# Sheet1.net
KiCad netlist of a schematic drawn in Altium Designer
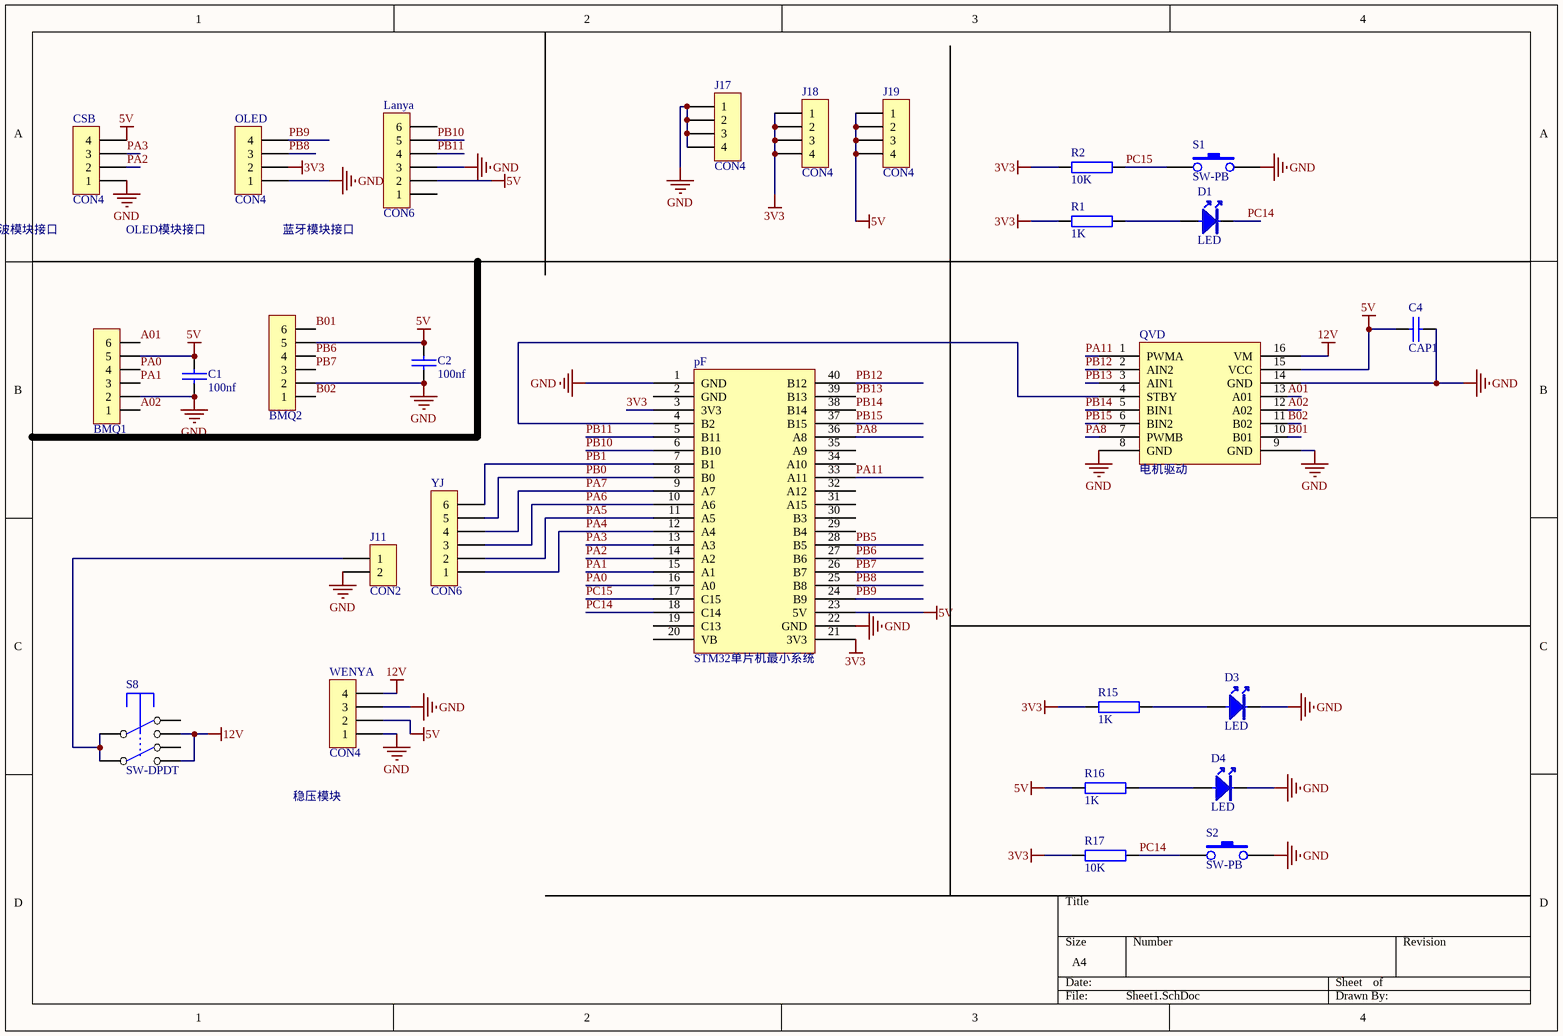
[diagram p0: Sheet1.SchDoc]

(export (version "E")
  (design (tool "Eeschema 10.0.6"))
  (components
    (comp (ref "BMQ1")
      (value "HDR-1X6")
      (footprint "XH2.54-WI-6P")
      (description "6P接插件")
      (fields (field (name "版权归属") "封装库来自淘宝 ID：黄晶宝石"))
      (libsource (lib "5.3 - 接插件-脚距2.54 (100mil) ") (part "Header 6"))
    )
    (comp (ref "BMQ2")
      (value "HDR-1X6")
      (footprint "XH2.54-WI-6P")
      (description "6P接插件")
      (fields (field (name "版权归属") "封装库来自淘宝 ID：黄晶宝石"))
      (libsource (lib "5.3 - 接插件-脚距2.54 (100mil) ") (part "Header 6"))
    )
    (comp (ref "C1") (value "100nf") (footprint "0603") (libsource (lib "电容") (part "CAP1")))
    (comp (ref "C2") (value "100nf") (footprint "0603") (libsource (lib "电容") (part "CAP1")))
    (comp (ref "C4") (value "CAP1") (footprint "0603") (libsource (lib "电容") (part "CAP1")))
    (comp (ref "CSB")
      (value "CON4")
      (footprint "HDR2.54-M-LI-4P")
      (description "Connector")
      (libsource (lib "接口") (part "CON4"))
    )
    (comp (ref "D1") (value "LED") (footprint "LED_0805") (libsource (lib "二极管") (part "LED")))
    (comp (ref "D3") (value "LED") (footprint "LED_0805") (libsource (lib "二极管") (part "LED")))
    (comp (ref "D4") (value "LED") (footprint "LED_0805") (libsource (lib "二极管") (part "LED")))
    (comp (ref "J11")
      (value "CON2")
      (footprint "KF128-5.08-2P")
      (description "Connector")
      (libsource (lib "接口") (part "CON2"))
    )
    (comp (ref "J17")
      (value "CON4")
      (footprint "sip-4")
      (description "Connector")
      (libsource (lib "排针") (part "CON4"))
    )
    (comp (ref "J18")
      (value "CON4")
      (footprint "sip-4")
      (description "Connector")
      (libsource (lib "排针") (part "CON4"))
    )
    (comp (ref "J19")
      (value "CON4")
      (footprint "sip-4")
      (description "Connector")
      (libsource (lib "排针") (part "CON4"))
    )
    (comp (ref "Lanya")
      (value "CON6")
      (footprint "HDR2.54-M-LI-6P")
      (description "Connector")
      (libsource (lib "接口") (part "CON6"))
    )
    (comp (ref "OLED")
      (value "CON4")
      (footprint "OLED")
      (description "Connector")
      (libsource (lib "接口") (part "CON4"))
    )
    (comp (ref "p")
      (value "STM32单片机最小系统")
      (footprint "PCBComponent_1 - duplicate")
      (libsource (lib "Schlib1") (part "Component_1"))
    )
    (comp (ref "QVD") (value "电机驱动") (footprint "DIP16P") (libsource (lib "Schlib2") (part "Component_1")))
    (comp (ref "R1") (value "1K") (footprint "0603") (description "电阻") (libsource (lib "电阻") (part "RES")))
    (comp (ref "R2") (value "10K") (footprint "0603") (description "电阻") (libsource (lib "电阻") (part "RES")))
    (comp (ref "R15") (value "1K") (footprint "0603") (description "电阻") (libsource (lib "电阻") (part "RES")))
    (comp (ref "R16") (value "1K") (footprint "0603") (description "电阻") (libsource (lib "电阻") (part "RES")))
    (comp (ref "R17") (value "10K") (footprint "0603") (description "电阻") (libsource (lib "电阻") (part "RES")))
    (comp (ref "S1") (value "SW-PB") (footprint "SW6*6") (libsource (lib "开关") (part "SW-PB")))
    (comp (ref "S2") (value "SW-PB") (footprint "SW6*6") (libsource (lib "开关") (part "SW-PB")))
    (comp (ref "S8") (value "SW-DPDT") (footprint "SWH7*7") (libsource (lib "开关.~(2)") (part "SW-DPDT")))
    (comp (ref "WENYA")
      (value "CON4")
      (footprint "WEI YA")
      (description "Connector")
      (libsource (lib "接口") (part "CON4"))
    )
    (comp (ref "YJ")
      (value "CON6")
      (footprint "sip-6")
      (description "Connector")
      (libsource (lib "排针") (part "CON6"))
    )
  )
  (nets
    (net (code "1") (name "/A01") (class "Default")
      (node (ref "BMQ1") (pin "6") (pinfunction "6_6") (pintype "passive"))
      (node (ref "QVD") (pin "13") (pinfunction "A01_13") (pintype "passive"))
    )
    (net (code "2") (name "/A02") (class "Default")
      (node (ref "BMQ1") (pin "1") (pinfunction "1_1") (pintype "passive"))
      (node (ref "QVD") (pin "12") (pinfunction "A02_12") (pintype "passive"))
    )
    (net (code "3") (name "/B01") (class "Default")
      (node (ref "BMQ2") (pin "6") (pinfunction "6_6") (pintype "passive"))
      (node (ref "QVD") (pin "10") (pinfunction "B01_10") (pintype "passive"))
    )
    (net (code "4") (name "/B02") (class "Default")
      (node (ref "BMQ2") (pin "1") (pinfunction "1_1") (pintype "passive"))
      (node (ref "QVD") (pin "11") (pinfunction "B02_11") (pintype "passive"))
    )
    (net (code "5") (name "/PA0") (class "Default")
      (node (ref "BMQ1") (pin "4") (pinfunction "4_4") (pintype "passive"))
      (node (ref "p") (pin "16") (pinfunction "A0_16") (pintype "passive"))
    )
    (net (code "6") (name "/PA1") (class "Default")
      (node (ref "BMQ1") (pin "3") (pinfunction "3_3") (pintype "passive"))
      (node (ref "p") (pin "15") (pinfunction "A1_15") (pintype "passive"))
    )
    (net (code "7") (name "/PA2") (class "Default")
      (node (ref "CSB") (pin "2") (pinfunction "2_2") (pintype "passive"))
      (node (ref "p") (pin "14") (pinfunction "A2_14") (pintype "passive"))
    )
    (net (code "8") (name "/PA3") (class "Default")
      (node (ref "CSB") (pin "3") (pinfunction "3_3") (pintype "passive"))
      (node (ref "p") (pin "13") (pinfunction "A3_13") (pintype "passive"))
    )
    (net (code "9") (name "/PA4") (class "Default")
      (node (ref "YJ") (pin "1") (pinfunction "1_1") (pintype "passive"))
      (node (ref "p") (pin "12") (pinfunction "A4_12") (pintype "passive"))
    )
    (net (code "10") (name "/PA5") (class "Default")
      (node (ref "YJ") (pin "2") (pinfunction "2_2") (pintype "passive"))
      (node (ref "p") (pin "11") (pinfunction "A5_11") (pintype "passive"))
    )
    (net (code "11") (name "/PA6") (class "Default")
      (node (ref "YJ") (pin "3") (pinfunction "3_3") (pintype "passive"))
      (node (ref "p") (pin "10") (pinfunction "A6_10") (pintype "passive"))
    )
    (net (code "12") (name "/PA7") (class "Default")
      (node (ref "YJ") (pin "4") (pinfunction "4_4") (pintype "passive"))
      (node (ref "p") (pin "9") (pinfunction "A7_9") (pintype "passive"))
    )
    (net (code "13") (name "/PA8") (class "Default")
      (node (ref "QVD") (pin "7") (pinfunction "PWMB_7") (pintype "passive"))
      (node (ref "p") (pin "36") (pinfunction "A8_36") (pintype "passive"))
    )
    (net (code "14") (name "/PA11") (class "Default")
      (node (ref "QVD") (pin "1") (pinfunction "PWMA_1") (pintype "passive"))
      (node (ref "p") (pin "33") (pinfunction "A11_33") (pintype "passive"))
    )
    (net (code "15") (name "/PB0") (class "Default")
      (node (ref "YJ") (pin "5") (pinfunction "5_5") (pintype "passive"))
      (node (ref "p") (pin "8") (pinfunction "B0_8") (pintype "passive"))
    )
    (net (code "16") (name "/PB1") (class "Default")
      (node (ref "YJ") (pin "6") (pinfunction "6_6") (pintype "passive"))
      (node (ref "p") (pin "7") (pinfunction "B1_7") (pintype "passive"))
    )
    (net (code "17") (name "/PB5") (class "Default")
      (node (ref "p") (pin "28") (pinfunction "B5_28") (pintype "passive"))
    )
    (net (code "18") (name "/PB6") (class "Default")
      (node (ref "BMQ2") (pin "4") (pinfunction "4_4") (pintype "passive"))
      (node (ref "p") (pin "27") (pinfunction "B6_27") (pintype "passive"))
    )
    (net (code "19") (name "/PB7") (class "Default")
      (node (ref "BMQ2") (pin "3") (pinfunction "3_3") (pintype "passive"))
      (node (ref "p") (pin "26") (pinfunction "B7_26") (pintype "passive"))
    )
    (net (code "20") (name "/PB8") (class "Default")
      (node (ref "OLED") (pin "3") (pinfunction "3_3") (pintype "passive"))
      (node (ref "p") (pin "25") (pinfunction "B8_25") (pintype "passive"))
    )
    (net (code "21") (name "/PB9") (class "Default")
      (node (ref "OLED") (pin "4") (pinfunction "4_4") (pintype "passive"))
      (node (ref "p") (pin "24") (pinfunction "B9_24") (pintype "passive"))
    )
    (net (code "22") (name "/PB10") (class "Default")
      (node (ref "Lanya") (pin "5") (pinfunction "5_5") (pintype "passive"))
      (node (ref "p") (pin "6") (pinfunction "B10_6") (pintype "passive"))
    )
    (net (code "23") (name "/PB11") (class "Default")
      (node (ref "Lanya") (pin "4") (pinfunction "4_4") (pintype "passive"))
      (node (ref "p") (pin "5") (pinfunction "B11_5") (pintype "passive"))
    )
    (net (code "24") (name "/PB12") (class "Default")
      (node (ref "QVD") (pin "2") (pinfunction "AIN2_2") (pintype "passive"))
      (node (ref "p") (pin "40") (pinfunction "B12_40") (pintype "passive"))
    )
    (net (code "25") (name "/PB13") (class "Default")
      (node (ref "QVD") (pin "3") (pinfunction "AIN1_3") (pintype "passive"))
      (node (ref "p") (pin "39") (pinfunction "B13_39") (pintype "passive"))
    )
    (net (code "26") (name "/PB14") (class "Default")
      (node (ref "QVD") (pin "5") (pinfunction "BIN1_5") (pintype "passive"))
      (node (ref "p") (pin "38") (pinfunction "B14_38") (pintype "passive"))
    )
    (net (code "27") (name "/PB15") (class "Default")
      (node (ref "QVD") (pin "6") (pinfunction "BIN2_6") (pintype "passive"))
      (node (ref "p") (pin "37") (pinfunction "B15_37") (pintype "passive"))
    )
    (net (code "28") (name "/PC14") (class "Default")
      (node (ref "D1") (pin "2") (pinfunction "2_2") (pintype "passive"))
      (node (ref "R17") (pin "2") (pinfunction "2_2") (pintype "passive"))
      (node (ref "S2") (pin "1") (pinfunction "1_1") (pintype "passive"))
      (node (ref "p") (pin "18") (pinfunction "C14_18") (pintype "passive"))
    )
    (net (code "29") (name "/PC15") (class "Default")
      (node (ref "R2") (pin "2") (pinfunction "2_2") (pintype "passive"))
      (node (ref "S1") (pin "1") (pinfunction "1_1") (pintype "passive"))
      (node (ref "p") (pin "17") (pinfunction "C15_17") (pintype "passive"))
    )
    (net (code "30") (name "3V3") (class "Default")
      (node (ref "J18") (pin "1") (pinfunction "1_1") (pintype "passive"))
      (node (ref "J18") (pin "2") (pinfunction "2_2") (pintype "passive"))
      (node (ref "J18") (pin "3") (pinfunction "3_3") (pintype "passive"))
      (node (ref "J18") (pin "4") (pinfunction "4_4") (pintype "passive"))
      (node (ref "OLED") (pin "2") (pinfunction "2_2") (pintype "passive"))
      (node (ref "R1") (pin "1") (pinfunction "1_1") (pintype "passive"))
      (node (ref "R15") (pin "1") (pinfunction "1_1") (pintype "passive"))
      (node (ref "R17") (pin "1") (pinfunction "1_1") (pintype "passive"))
      (node (ref "R2") (pin "1") (pinfunction "1_1") (pintype "passive"))
      (node (ref "p") (pin "21") (pinfunction "3V3_21") (pintype "passive"))
      (node (ref "p") (pin "3") (pinfunction "3V3_3") (pintype "passive"))
    )
    (net (code "31") (name "5V") (class "Default")
      (node (ref "BMQ1") (pin "5") (pinfunction "5_5") (pintype "passive"))
      (node (ref "BMQ2") (pin "5") (pinfunction "5_5") (pintype "passive"))
      (node (ref "C1") (pin "1") (pinfunction "1_1") (pintype "passive"))
      (node (ref "C2") (pin "1") (pinfunction "1_1") (pintype "passive"))
      (node (ref "C4") (pin "1") (pinfunction "1_1") (pintype "passive"))
      (node (ref "CSB") (pin "4") (pinfunction "4_4") (pintype "passive"))
      (node (ref "J19") (pin "1") (pinfunction "1_1") (pintype "passive"))
      (node (ref "J19") (pin "2") (pinfunction "2_2") (pintype "passive"))
      (node (ref "J19") (pin "3") (pinfunction "3_3") (pintype "passive"))
      (node (ref "J19") (pin "4") (pinfunction "4_4") (pintype "passive"))
      (node (ref "Lanya") (pin "2") (pinfunction "2_2") (pintype "passive"))
      (node (ref "QVD") (pin "15") (pinfunction "VCC_15") (pintype "passive"))
      (node (ref "R16") (pin "1") (pinfunction "1_1") (pintype "passive"))
      (node (ref "WENYA") (pin "2") (pinfunction "2_2") (pintype "passive"))
      (node (ref "p") (pin "23") (pinfunction "5V_23") (pintype "passive"))
    )
    (net (code "32") (name "12V") (class "Default")
      (node (ref "QVD") (pin "16") (pinfunction "VM_16") (pintype "passive"))
      (node (ref "S8") (pin "3") (pinfunction "3_3") (pintype "passive"))
      (node (ref "S8") (pin "4") (pinfunction "4_4") (pintype "passive"))
      (node (ref "WENYA") (pin "4") (pinfunction "4_4") (pintype "passive"))
    )
    (net (code "33") (name "GND") (class "Default")
      (node (ref "BMQ1") (pin "2") (pinfunction "2_2") (pintype "passive"))
      (node (ref "BMQ2") (pin "2") (pinfunction "2_2") (pintype "passive"))
      (node (ref "C1") (pin "2") (pinfunction "2_2") (pintype "passive"))
      (node (ref "C2") (pin "2") (pinfunction "2_2") (pintype "passive"))
      (node (ref "C4") (pin "2") (pinfunction "2_2") (pintype "passive"))
      (node (ref "CSB") (pin "1") (pinfunction "1_1") (pintype "passive"))
      (node (ref "D3") (pin "2") (pinfunction "2_2") (pintype "passive"))
      (node (ref "D4") (pin "2") (pinfunction "2_2") (pintype "passive"))
      (node (ref "J11") (pin "2") (pinfunction "2_2") (pintype "passive"))
      (node (ref "J17") (pin "1") (pinfunction "1_1") (pintype "passive"))
      (node (ref "J17") (pin "2") (pinfunction "2_2") (pintype "passive"))
      (node (ref "J17") (pin "3") (pinfunction "3_3") (pintype "passive"))
      (node (ref "J17") (pin "4") (pinfunction "4_4") (pintype "passive"))
      (node (ref "Lanya") (pin "3") (pinfunction "3_3") (pintype "passive"))
      (node (ref "OLED") (pin "1") (pinfunction "1_1") (pintype "passive"))
      (node (ref "QVD") (pin "14") (pinfunction "GND_14") (pintype "passive"))
      (node (ref "QVD") (pin "8") (pinfunction "GND_8") (pintype "passive"))
      (node (ref "QVD") (pin "9") (pinfunction "GND_9") (pintype "passive"))
      (node (ref "S1") (pin "2") (pinfunction "2_2") (pintype "passive"))
      (node (ref "S2") (pin "2") (pinfunction "2_2") (pintype "passive"))
      (node (ref "WENYA") (pin "1") (pinfunction "1_1") (pintype "passive"))
      (node (ref "WENYA") (pin "3") (pinfunction "3_3") (pintype "passive"))
      (node (ref "p") (pin "1") (pinfunction "GND_1") (pintype "passive"))
      (node (ref "p") (pin "22") (pinfunction "GND_22") (pintype "passive"))
    )
    (net (code "34") (name "Net-(D1-Pad1)") (class "Default")
      (node (ref "D1") (pin "1") (pinfunction "1_1") (pintype "passive"))
      (node (ref "R1") (pin "2") (pinfunction "2_2") (pintype "passive"))
    )
    (net (code "35") (name "Net-(D3-Pad1)") (class "Default")
      (node (ref "D3") (pin "1") (pinfunction "1_1") (pintype "passive"))
      (node (ref "R15") (pin "2") (pinfunction "2_2") (pintype "passive"))
    )
    (net (code "36") (name "Net-(D4-Pad1)") (class "Default")
      (node (ref "D4") (pin "1") (pinfunction "1_1") (pintype "passive"))
      (node (ref "R16") (pin "2") (pinfunction "2_2") (pintype "passive"))
    )
    (net (code "37") (name "Net-(J11-Pad1)") (class "Default")
      (node (ref "J11") (pin "1") (pinfunction "1_1") (pintype "passive"))
      (node (ref "S8") (pin "2") (pinfunction "2_2") (pintype "passive"))
      (node (ref "S8") (pin "5") (pinfunction "5_5") (pintype "passive"))
    )
    (net (code "38") (name "Net-(QVD-STBY)") (class "Default")
      (node (ref "QVD") (pin "4") (pinfunction "STBY_4") (pintype "passive"))
      (node (ref "p") (pin "4") (pinfunction "B2_4") (pintype "passive"))
    )
    (net (code "39") (name "unconnected-(Lanya-Pad1)") (class "Default")
      (node (ref "Lanya") (pin "1") (pinfunction "1_1") (pintype "passive"))
    )
    (net (code "40") (name "unconnected-(Lanya-Pad6)") (class "Default")
      (node (ref "Lanya") (pin "6") (pinfunction "6_6") (pintype "passive"))
    )
    (net (code "41") (name "unconnected-(S8-Pad1)") (class "Default")
      (node (ref "S8") (pin "1") (pinfunction "1_1") (pintype "passive"))
    )
    (net (code "42") (name "unconnected-(S8-Pad6)") (class "Default")
      (node (ref "S8") (pin "6") (pinfunction "6_6") (pintype "passive"))
    )
    (net (code "43") (name "unconnected-(pF-A9-Pad35)") (class "Default")
      (node (ref "p") (pin "35") (pinfunction "A9_35") (pintype "passive"))
    )
    (net (code "44") (name "unconnected-(pF-A10-Pad34)") (class "Default")
      (node (ref "p") (pin "34") (pinfunction "A10_34") (pintype "passive"))
    )
    (net (code "45") (name "unconnected-(pF-A12-Pad32)") (class "Default")
      (node (ref "p") (pin "32") (pinfunction "A12_32") (pintype "passive"))
    )
    (net (code "46") (name "unconnected-(pF-A15-Pad31)") (class "Default")
      (node (ref "p") (pin "31") (pinfunction "A15_31") (pintype "passive"))
    )
    (net (code "47") (name "unconnected-(pF-B3-Pad30)") (class "Default")
      (node (ref "p") (pin "30") (pinfunction "B3_30") (pintype "passive"))
    )
    (net (code "48") (name "unconnected-(pF-B4-Pad29)") (class "Default")
      (node (ref "p") (pin "29") (pinfunction "B4_29") (pintype "passive"))
    )
    (net (code "49") (name "unconnected-(pF-C13-Pad19)") (class "Default")
      (node (ref "p") (pin "19") (pinfunction "C13_19") (pintype "passive"))
    )
    (net (code "50") (name "unconnected-(pF-GND-Pad2)") (class "Default")
      (node (ref "p") (pin "2") (pinfunction "GND_2") (pintype "passive"))
    )
    (net (code "51") (name "unconnected-(pF-VB-Pad20)") (class "Default")
      (node (ref "p") (pin "20") (pinfunction "VB_20") (pintype "passive"))
    )
  )
)
